# clock.net
KiCad netlist of a schematic drawn in EAGLE
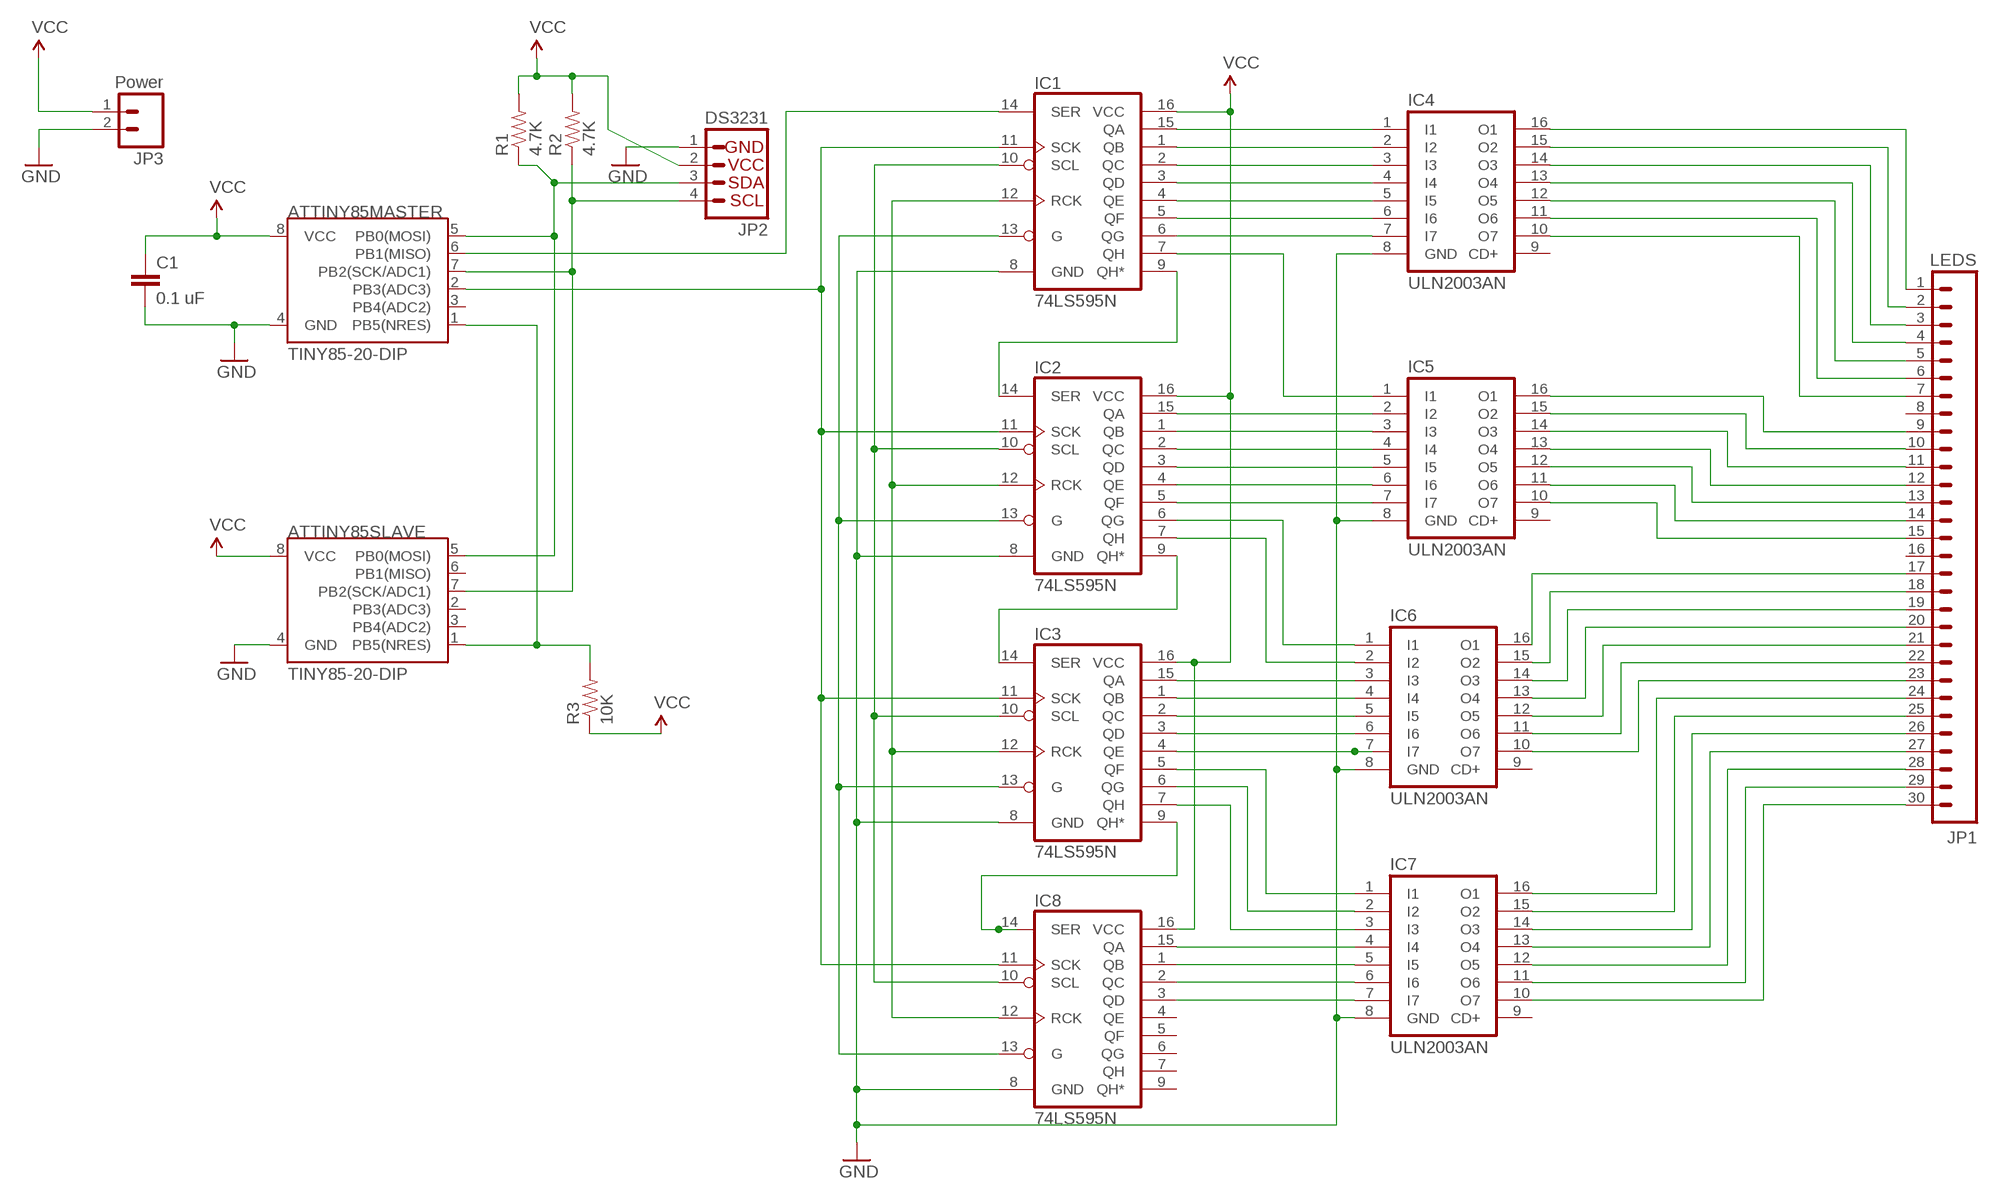
[diagram p0: schematic, sheet 1]

(export (version "E")
  (design (tool "Eeschema 10.0.6"))
  (components
    (comp (ref "ATTINY85MASTER")
      (value "TINY85-20-DIP")
      (footprint "eagle-import:DIP08")
      (libsource (lib "eagle-import") (part "ATTINY45TINY85-20-DIP"))
    )
    (comp (ref "ATTINY85SLAVE")
      (value "TINY85-20-DIP")
      (footprint "eagle-import:DIP08")
      (libsource (lib "eagle-import") (part "ATTINY45TINY85-20-DIP"))
    )
    (comp (ref "C1")
      (value "0.1 uF")
      (footprint "eagle-import:CAP-PTH-SMALL")
      (libsource (lib "eagle-import") (part "CAPPTH"))
    )
    (comp (ref "IC1")
      (value "74LS595N")
      (footprint "eagle-import:DIL16")
      (libsource (lib "eagle-import") (part "74595NLS"))
    )
    (comp (ref "IC2")
      (value "74LS595N")
      (footprint "eagle-import:DIL16")
      (libsource (lib "eagle-import") (part "74595NLS"))
    )
    (comp (ref "IC3")
      (value "74LS595N")
      (footprint "eagle-import:DIL16")
      (libsource (lib "eagle-import") (part "74595NLS"))
    )
    (comp (ref "IC4")
      (value "ULN2003AN")
      (footprint "eagle-import:DIL16")
      (libsource (lib "eagle-import") (part "ULN2003AN"))
    )
    (comp (ref "IC5")
      (value "ULN2003AN")
      (footprint "eagle-import:DIL16")
      (libsource (lib "eagle-import") (part "ULN2003AN"))
    )
    (comp (ref "IC6")
      (value "ULN2003AN")
      (footprint "eagle-import:DIL16")
      (libsource (lib "eagle-import") (part "ULN2003AN"))
    )
    (comp (ref "IC7")
      (value "ULN2003AN")
      (footprint "eagle-import:DIL16")
      (libsource (lib "eagle-import") (part "ULN2003AN"))
    )
    (comp (ref "IC8")
      (value "74LS595N")
      (footprint "eagle-import:DIL16")
      (libsource (lib "eagle-import") (part "74595NLS"))
    )
    (comp (ref "JP1")
      (value "LEDS")
      (footprint "eagle-import:1X30")
      (libsource (lib "eagle-import") (part "M30"))
    )
    (comp (ref "JP2")
      (value "DS3231")
      (footprint "eagle-import:1X04")
      (libsource (lib "eagle-import") (part "I2C_STANDARD"))
    )
    (comp (ref "JP3")
      (value "Power")
      (footprint "eagle-import:1X02_LONGPADS")
      (libsource (lib "eagle-import") (part "M02PTH3"))
    )
    (comp (ref "R1")
      (value "4.7K")
      (footprint "eagle-import:AXIAL-0.4")
      (libsource (lib "eagle-import") (part "RESISTORPTH-1/4W"))
    )
    (comp (ref "R2")
      (value "4.7K")
      (footprint "eagle-import:AXIAL-0.4")
      (libsource (lib "eagle-import") (part "RESISTORPTH-1/4W"))
    )
    (comp (ref "R3")
      (value "10K")
      (footprint "eagle-import:AXIAL-0.4")
      (libsource (lib "eagle-import") (part "RESISTORPTH-1/4W"))
    )
  )
  (nets
    (net (code "1") (name "GND") (class "Default")
      (node (ref "ATTINY85MASTER") (pin "4") (pinfunction "GND_4") (pintype "bidirectional"))
      (node (ref "ATTINY85SLAVE") (pin "4") (pinfunction "GND_4") (pintype "bidirectional"))
      (node (ref "C1") (pin "2") (pinfunction "2_2") (pintype "passive"))
      (node (ref "IC1") (pin "8") (pinfunction "GND_8") (pintype "power_in"))
      (node (ref "IC2") (pin "8") (pinfunction "GND_8") (pintype "power_in"))
      (node (ref "IC3") (pin "8") (pinfunction "GND_8") (pintype "power_in"))
      (node (ref "IC4") (pin "8") (pinfunction "GND_8") (pintype "power_in"))
      (node (ref "IC5") (pin "8") (pinfunction "GND_8") (pintype "power_in"))
      (node (ref "IC6") (pin "8") (pinfunction "GND_8") (pintype "power_in"))
      (node (ref "IC7") (pin "8") (pinfunction "GND_8") (pintype "power_in"))
      (node (ref "IC8") (pin "8") (pinfunction "GND_8") (pintype "power_in"))
      (node (ref "JP2") (pin "1") (pinfunction "1_1") (pintype "passive"))
      (node (ref "JP3") (pin "2") (pinfunction "2_2") (pintype "passive"))
    )
    (net (code "2") (name "Net-(ATTINY85MASTER-PB0(MOSI))") (class "Default")
      (node (ref "ATTINY85MASTER") (pin "5") (pinfunction "PB0(MOSI)_5") (pintype "bidirectional"))
      (node (ref "ATTINY85SLAVE") (pin "5") (pinfunction "PB0(MOSI)_5") (pintype "bidirectional"))
      (node (ref "JP2") (pin "3") (pinfunction "3_3") (pintype "passive"))
      (node (ref "R1") (pin "P$1") (pinfunction "1_P$1") (pintype "passive"))
    )
    (net (code "3") (name "Net-(ATTINY85MASTER-PB1(MISO))") (class "Default")
      (node (ref "ATTINY85MASTER") (pin "6") (pinfunction "PB1(MISO)_6") (pintype "bidirectional"))
      (node (ref "IC1") (pin "14") (pinfunction "SER_14") (pintype "input"))
    )
    (net (code "4") (name "Net-(ATTINY85MASTER-PB2(SCK{slash}ADC1))") (class "Default")
      (node (ref "ATTINY85MASTER") (pin "7") (pinfunction "PB2(SCK/ADC1)_7") (pintype "bidirectional"))
      (node (ref "ATTINY85SLAVE") (pin "7") (pinfunction "PB2(SCK/ADC1)_7") (pintype "bidirectional"))
      (node (ref "JP2") (pin "4") (pinfunction "4_4") (pintype "passive"))
      (node (ref "R2") (pin "P$1") (pinfunction "1_P$1") (pintype "passive"))
    )
    (net (code "5") (name "Net-(ATTINY85MASTER-PB3(ADC3))") (class "Default")
      (node (ref "ATTINY85MASTER") (pin "2") (pinfunction "PB3(ADC3)_2") (pintype "bidirectional"))
      (node (ref "IC1") (pin "11") (pinfunction "SCK_11") (pintype "input"))
      (node (ref "IC2") (pin "11") (pinfunction "SCK_11") (pintype "input"))
      (node (ref "IC3") (pin "11") (pinfunction "SCK_11") (pintype "input"))
      (node (ref "IC8") (pin "11") (pinfunction "SCK_11") (pintype "input"))
    )
    (net (code "6") (name "Net-(ATTINY85MASTER-PB5(NRES))") (class "Default")
      (node (ref "ATTINY85MASTER") (pin "1") (pinfunction "PB5(NRES)_1") (pintype "bidirectional"))
      (node (ref "ATTINY85SLAVE") (pin "1") (pinfunction "PB5(NRES)_1") (pintype "bidirectional"))
      (node (ref "R3") (pin "P$2") (pinfunction "2_P$2") (pintype "passive"))
    )
    (net (code "7") (name "Net-(IC1-G)") (class "Default")
      (node (ref "IC1") (pin "13") (pinfunction "G_13") (pintype "input"))
      (node (ref "IC2") (pin "13") (pinfunction "G_13") (pintype "input"))
      (node (ref "IC3") (pin "13") (pinfunction "G_13") (pintype "input"))
      (node (ref "IC8") (pin "13") (pinfunction "G_13") (pintype "input"))
    )
    (net (code "8") (name "Net-(IC1-QA)") (class "Default")
      (node (ref "IC1") (pin "15") (pinfunction "QA_15") (pintype "tri_state"))
      (node (ref "IC4") (pin "1") (pinfunction "I1_1") (pintype "input"))
    )
    (net (code "9") (name "Net-(IC1-QB)") (class "Default")
      (node (ref "IC1") (pin "1") (pinfunction "QB_1") (pintype "tri_state"))
      (node (ref "IC4") (pin "2") (pinfunction "I2_2") (pintype "input"))
    )
    (net (code "10") (name "Net-(IC1-QC)") (class "Default")
      (node (ref "IC1") (pin "2") (pinfunction "QC_2") (pintype "tri_state"))
      (node (ref "IC4") (pin "3") (pinfunction "I3_3") (pintype "input"))
    )
    (net (code "11") (name "Net-(IC1-QD)") (class "Default")
      (node (ref "IC1") (pin "3") (pinfunction "QD_3") (pintype "tri_state"))
      (node (ref "IC4") (pin "4") (pinfunction "I4_4") (pintype "input"))
    )
    (net (code "12") (name "Net-(IC1-QE)") (class "Default")
      (node (ref "IC1") (pin "4") (pinfunction "QE_4") (pintype "tri_state"))
      (node (ref "IC4") (pin "5") (pinfunction "I5_5") (pintype "input"))
    )
    (net (code "13") (name "Net-(IC1-QF)") (class "Default")
      (node (ref "IC1") (pin "5") (pinfunction "QF_5") (pintype "tri_state"))
      (node (ref "IC4") (pin "6") (pinfunction "I6_6") (pintype "input"))
    )
    (net (code "14") (name "Net-(IC1-QG)") (class "Default")
      (node (ref "IC1") (pin "6") (pinfunction "QG_6") (pintype "tri_state"))
      (node (ref "IC4") (pin "7") (pinfunction "I7_7") (pintype "input"))
    )
    (net (code "15") (name "Net-(IC1-QH)") (class "Default")
      (node (ref "IC1") (pin "7") (pinfunction "QH_7") (pintype "tri_state"))
      (node (ref "IC5") (pin "1") (pinfunction "I1_1") (pintype "input"))
    )
    (net (code "16") (name "Net-(IC1-QH*)") (class "Default")
      (node (ref "IC1") (pin "9") (pinfunction "QH*_9") (pintype "tri_state"))
      (node (ref "IC2") (pin "14") (pinfunction "SER_14") (pintype "input"))
    )
    (net (code "17") (name "Net-(IC1-RCK)") (class "Default")
      (node (ref "IC1") (pin "12") (pinfunction "RCK_12") (pintype "input"))
      (node (ref "IC2") (pin "12") (pinfunction "RCK_12") (pintype "input"))
      (node (ref "IC3") (pin "12") (pinfunction "RCK_12") (pintype "input"))
      (node (ref "IC8") (pin "12") (pinfunction "RCK_12") (pintype "input"))
    )
    (net (code "18") (name "Net-(IC1-SCL)") (class "Default")
      (node (ref "IC1") (pin "10") (pinfunction "SCL_10") (pintype "input"))
      (node (ref "IC2") (pin "10") (pinfunction "SCL_10") (pintype "input"))
      (node (ref "IC3") (pin "10") (pinfunction "SCL_10") (pintype "input"))
      (node (ref "IC8") (pin "10") (pinfunction "SCL_10") (pintype "input"))
    )
    (net (code "19") (name "Net-(IC2-QA)") (class "Default")
      (node (ref "IC2") (pin "15") (pinfunction "QA_15") (pintype "tri_state"))
      (node (ref "IC5") (pin "2") (pinfunction "I2_2") (pintype "input"))
    )
    (net (code "20") (name "Net-(IC2-QB)") (class "Default")
      (node (ref "IC2") (pin "1") (pinfunction "QB_1") (pintype "tri_state"))
      (node (ref "IC5") (pin "3") (pinfunction "I3_3") (pintype "input"))
    )
    (net (code "21") (name "Net-(IC2-QC)") (class "Default")
      (node (ref "IC2") (pin "2") (pinfunction "QC_2") (pintype "tri_state"))
      (node (ref "IC5") (pin "4") (pinfunction "I4_4") (pintype "input"))
    )
    (net (code "22") (name "Net-(IC2-QD)") (class "Default")
      (node (ref "IC2") (pin "3") (pinfunction "QD_3") (pintype "tri_state"))
      (node (ref "IC5") (pin "5") (pinfunction "I5_5") (pintype "input"))
    )
    (net (code "23") (name "Net-(IC2-QE)") (class "Default")
      (node (ref "IC2") (pin "4") (pinfunction "QE_4") (pintype "tri_state"))
      (node (ref "IC5") (pin "6") (pinfunction "I6_6") (pintype "input"))
    )
    (net (code "24") (name "Net-(IC2-QF)") (class "Default")
      (node (ref "IC2") (pin "5") (pinfunction "QF_5") (pintype "tri_state"))
      (node (ref "IC5") (pin "7") (pinfunction "I7_7") (pintype "input"))
    )
    (net (code "25") (name "Net-(IC2-QG)") (class "Default")
      (node (ref "IC2") (pin "6") (pinfunction "QG_6") (pintype "tri_state"))
      (node (ref "IC6") (pin "1") (pinfunction "I1_1") (pintype "input"))
    )
    (net (code "26") (name "Net-(IC2-QH)") (class "Default")
      (node (ref "IC2") (pin "7") (pinfunction "QH_7") (pintype "tri_state"))
      (node (ref "IC6") (pin "2") (pinfunction "I2_2") (pintype "input"))
    )
    (net (code "27") (name "Net-(IC2-QH*)") (class "Default")
      (node (ref "IC2") (pin "9") (pinfunction "QH*_9") (pintype "tri_state"))
      (node (ref "IC3") (pin "14") (pinfunction "SER_14") (pintype "input"))
    )
    (net (code "28") (name "Net-(IC3-QA)") (class "Default")
      (node (ref "IC3") (pin "15") (pinfunction "QA_15") (pintype "tri_state"))
      (node (ref "IC6") (pin "3") (pinfunction "I3_3") (pintype "input"))
    )
    (net (code "29") (name "Net-(IC3-QB)") (class "Default")
      (node (ref "IC3") (pin "1") (pinfunction "QB_1") (pintype "tri_state"))
      (node (ref "IC6") (pin "4") (pinfunction "I4_4") (pintype "input"))
    )
    (net (code "30") (name "Net-(IC3-QC)") (class "Default")
      (node (ref "IC3") (pin "2") (pinfunction "QC_2") (pintype "tri_state"))
      (node (ref "IC6") (pin "5") (pinfunction "I5_5") (pintype "input"))
    )
    (net (code "31") (name "Net-(IC3-QD)") (class "Default")
      (node (ref "IC3") (pin "3") (pinfunction "QD_3") (pintype "tri_state"))
      (node (ref "IC6") (pin "6") (pinfunction "I6_6") (pintype "input"))
    )
    (net (code "32") (name "Net-(IC3-QE)") (class "Default")
      (node (ref "IC3") (pin "4") (pinfunction "QE_4") (pintype "tri_state"))
      (node (ref "IC6") (pin "7") (pinfunction "I7_7") (pintype "input"))
    )
    (net (code "33") (name "Net-(IC3-QF)") (class "Default")
      (node (ref "IC3") (pin "5") (pinfunction "QF_5") (pintype "tri_state"))
      (node (ref "IC7") (pin "1") (pinfunction "I1_1") (pintype "input"))
    )
    (net (code "34") (name "Net-(IC3-QG)") (class "Default")
      (node (ref "IC3") (pin "6") (pinfunction "QG_6") (pintype "tri_state"))
      (node (ref "IC7") (pin "2") (pinfunction "I2_2") (pintype "input"))
    )
    (net (code "35") (name "Net-(IC3-QH)") (class "Default")
      (node (ref "IC3") (pin "7") (pinfunction "QH_7") (pintype "tri_state"))
      (node (ref "IC7") (pin "3") (pinfunction "I3_3") (pintype "input"))
    )
    (net (code "36") (name "Net-(IC3-QH*)") (class "Default")
      (node (ref "IC3") (pin "9") (pinfunction "QH*_9") (pintype "tri_state"))
      (node (ref "IC8") (pin "14") (pinfunction "SER_14") (pintype "input"))
    )
    (net (code "37") (name "Net-(IC4-O1)") (class "Default")
      (node (ref "IC4") (pin "16") (pinfunction "O1_16") (pintype "open_collector"))
      (node (ref "JP1") (pin "1") (pinfunction "1_1") (pintype "passive"))
    )
    (net (code "38") (name "Net-(IC4-O2)") (class "Default")
      (node (ref "IC4") (pin "15") (pinfunction "O2_15") (pintype "open_collector"))
      (node (ref "JP1") (pin "2") (pinfunction "2_2") (pintype "passive"))
    )
    (net (code "39") (name "Net-(IC4-O3)") (class "Default")
      (node (ref "IC4") (pin "14") (pinfunction "O3_14") (pintype "open_collector"))
      (node (ref "JP1") (pin "3") (pinfunction "3_3") (pintype "passive"))
    )
    (net (code "40") (name "Net-(IC4-O4)") (class "Default")
      (node (ref "IC4") (pin "13") (pinfunction "O4_13") (pintype "open_collector"))
      (node (ref "JP1") (pin "4") (pinfunction "4_4") (pintype "passive"))
    )
    (net (code "41") (name "Net-(IC4-O5)") (class "Default")
      (node (ref "IC4") (pin "12") (pinfunction "O5_12") (pintype "open_collector"))
      (node (ref "JP1") (pin "5") (pinfunction "5_5") (pintype "passive"))
    )
    (net (code "42") (name "Net-(IC4-O6)") (class "Default")
      (node (ref "IC4") (pin "11") (pinfunction "O6_11") (pintype "open_collector"))
      (node (ref "JP1") (pin "6") (pinfunction "6_6") (pintype "passive"))
    )
    (net (code "43") (name "Net-(IC4-O7)") (class "Default")
      (node (ref "IC4") (pin "10") (pinfunction "O7_10") (pintype "open_collector"))
      (node (ref "JP1") (pin "7") (pinfunction "7_7") (pintype "passive"))
    )
    (net (code "44") (name "Net-(IC5-O1)") (class "Default")
      (node (ref "IC5") (pin "16") (pinfunction "O1_16") (pintype "open_collector"))
      (node (ref "JP1") (pin "9") (pinfunction "9_9") (pintype "passive"))
    )
    (net (code "45") (name "Net-(IC5-O2)") (class "Default")
      (node (ref "IC5") (pin "15") (pinfunction "O2_15") (pintype "open_collector"))
      (node (ref "JP1") (pin "10") (pinfunction "10_10") (pintype "passive"))
    )
    (net (code "46") (name "Net-(IC5-O3)") (class "Default")
      (node (ref "IC5") (pin "14") (pinfunction "O3_14") (pintype "open_collector"))
      (node (ref "JP1") (pin "11") (pinfunction "11_11") (pintype "passive"))
    )
    (net (code "47") (name "Net-(IC5-O4)") (class "Default")
      (node (ref "IC5") (pin "13") (pinfunction "O4_13") (pintype "open_collector"))
      (node (ref "JP1") (pin "12") (pinfunction "12_12") (pintype "passive"))
    )
    (net (code "48") (name "Net-(IC5-O5)") (class "Default")
      (node (ref "IC5") (pin "12") (pinfunction "O5_12") (pintype "open_collector"))
      (node (ref "JP1") (pin "13") (pinfunction "13_13") (pintype "passive"))
    )
    (net (code "49") (name "Net-(IC5-O6)") (class "Default")
      (node (ref "IC5") (pin "11") (pinfunction "O6_11") (pintype "open_collector"))
      (node (ref "JP1") (pin "14") (pinfunction "14_14") (pintype "passive"))
    )
    (net (code "50") (name "Net-(IC5-O7)") (class "Default")
      (node (ref "IC5") (pin "10") (pinfunction "O7_10") (pintype "open_collector"))
      (node (ref "JP1") (pin "15") (pinfunction "15_15") (pintype "passive"))
    )
    (net (code "51") (name "Net-(IC6-O1)") (class "Default")
      (node (ref "IC6") (pin "16") (pinfunction "O1_16") (pintype "open_collector"))
      (node (ref "JP1") (pin "17") (pinfunction "17_17") (pintype "passive"))
    )
    (net (code "52") (name "Net-(IC6-O2)") (class "Default")
      (node (ref "IC6") (pin "15") (pinfunction "O2_15") (pintype "open_collector"))
      (node (ref "JP1") (pin "18") (pinfunction "18_18") (pintype "passive"))
    )
    (net (code "53") (name "Net-(IC6-O3)") (class "Default")
      (node (ref "IC6") (pin "14") (pinfunction "O3_14") (pintype "open_collector"))
      (node (ref "JP1") (pin "19") (pinfunction "19_19") (pintype "passive"))
    )
    (net (code "54") (name "Net-(IC6-O4)") (class "Default")
      (node (ref "IC6") (pin "13") (pinfunction "O4_13") (pintype "open_collector"))
      (node (ref "JP1") (pin "20") (pinfunction "20_20") (pintype "passive"))
    )
    (net (code "55") (name "Net-(IC6-O5)") (class "Default")
      (node (ref "IC6") (pin "12") (pinfunction "O5_12") (pintype "open_collector"))
      (node (ref "JP1") (pin "21") (pinfunction "21_21") (pintype "passive"))
    )
    (net (code "56") (name "Net-(IC6-O6)") (class "Default")
      (node (ref "IC6") (pin "11") (pinfunction "O6_11") (pintype "open_collector"))
      (node (ref "JP1") (pin "22") (pinfunction "22_22") (pintype "passive"))
    )
    (net (code "57") (name "Net-(IC6-O7)") (class "Default")
      (node (ref "IC6") (pin "10") (pinfunction "O7_10") (pintype "open_collector"))
      (node (ref "JP1") (pin "23") (pinfunction "23_23") (pintype "passive"))
    )
    (net (code "58") (name "Net-(IC7-I4)") (class "Default")
      (node (ref "IC7") (pin "4") (pinfunction "I4_4") (pintype "input"))
      (node (ref "IC8") (pin "15") (pinfunction "QA_15") (pintype "tri_state"))
    )
    (net (code "59") (name "Net-(IC7-I5)") (class "Default")
      (node (ref "IC7") (pin "5") (pinfunction "I5_5") (pintype "input"))
      (node (ref "IC8") (pin "1") (pinfunction "QB_1") (pintype "tri_state"))
    )
    (net (code "60") (name "Net-(IC7-I6)") (class "Default")
      (node (ref "IC7") (pin "6") (pinfunction "I6_6") (pintype "input"))
      (node (ref "IC8") (pin "2") (pinfunction "QC_2") (pintype "tri_state"))
    )
    (net (code "61") (name "Net-(IC7-I7)") (class "Default")
      (node (ref "IC7") (pin "7") (pinfunction "I7_7") (pintype "input"))
      (node (ref "IC8") (pin "3") (pinfunction "QD_3") (pintype "tri_state"))
    )
    (net (code "62") (name "Net-(IC7-O1)") (class "Default")
      (node (ref "IC7") (pin "16") (pinfunction "O1_16") (pintype "open_collector"))
      (node (ref "JP1") (pin "24") (pinfunction "24_24") (pintype "passive"))
    )
    (net (code "63") (name "Net-(IC7-O2)") (class "Default")
      (node (ref "IC7") (pin "15") (pinfunction "O2_15") (pintype "open_collector"))
      (node (ref "JP1") (pin "25") (pinfunction "25_25") (pintype "passive"))
    )
    (net (code "64") (name "Net-(IC7-O3)") (class "Default")
      (node (ref "IC7") (pin "14") (pinfunction "O3_14") (pintype "open_collector"))
      (node (ref "JP1") (pin "26") (pinfunction "26_26") (pintype "passive"))
    )
    (net (code "65") (name "Net-(IC7-O4)") (class "Default")
      (node (ref "IC7") (pin "13") (pinfunction "O4_13") (pintype "open_collector"))
      (node (ref "JP1") (pin "27") (pinfunction "27_27") (pintype "passive"))
    )
    (net (code "66") (name "Net-(IC7-O5)") (class "Default")
      (node (ref "IC7") (pin "12") (pinfunction "O5_12") (pintype "open_collector"))
      (node (ref "JP1") (pin "28") (pinfunction "28_28") (pintype "passive"))
    )
    (net (code "67") (name "Net-(IC7-O6)") (class "Default")
      (node (ref "IC7") (pin "11") (pinfunction "O6_11") (pintype "open_collector"))
      (node (ref "JP1") (pin "29") (pinfunction "29_29") (pintype "passive"))
    )
    (net (code "68") (name "Net-(IC7-O7)") (class "Default")
      (node (ref "IC7") (pin "10") (pinfunction "O7_10") (pintype "open_collector"))
      (node (ref "JP1") (pin "30") (pinfunction "30_30") (pintype "passive"))
    )
    (net (code "69") (name "VCC") (class "Default")
      (node (ref "ATTINY85MASTER") (pin "8") (pinfunction "VCC_8") (pintype "bidirectional"))
      (node (ref "ATTINY85SLAVE") (pin "8") (pinfunction "VCC_8") (pintype "bidirectional"))
      (node (ref "C1") (pin "1") (pinfunction "1_1") (pintype "passive"))
      (node (ref "IC1") (pin "16") (pinfunction "VCC_16") (pintype "power_in"))
      (node (ref "IC2") (pin "16") (pinfunction "VCC_16") (pintype "power_in"))
      (node (ref "IC3") (pin "16") (pinfunction "VCC_16") (pintype "power_in"))
      (node (ref "IC8") (pin "16") (pinfunction "VCC_16") (pintype "power_in"))
      (node (ref "JP2") (pin "2") (pinfunction "2_2") (pintype "passive"))
      (node (ref "JP3") (pin "1") (pinfunction "1_1") (pintype "passive"))
      (node (ref "R1") (pin "P$2") (pinfunction "2_P$2") (pintype "passive"))
      (node (ref "R2") (pin "P$2") (pinfunction "2_P$2") (pintype "passive"))
      (node (ref "R3") (pin "P$1") (pinfunction "1_P$1") (pintype "passive"))
    )
    (net (code "70") (name "unconnected-(ATTINY85MASTER-PB4(ADC2)-Pad3)") (class "Default")
      (node (ref "ATTINY85MASTER") (pin "3") (pinfunction "PB4(ADC2)_3") (pintype "bidirectional"))
    )
    (net (code "71") (name "unconnected-(ATTINY85SLAVE-PB1(MISO)-Pad6)") (class "Default")
      (node (ref "ATTINY85SLAVE") (pin "6") (pinfunction "PB1(MISO)_6") (pintype "bidirectional"))
    )
    (net (code "72") (name "unconnected-(ATTINY85SLAVE-PB3(ADC3)-Pad2)") (class "Default")
      (node (ref "ATTINY85SLAVE") (pin "2") (pinfunction "PB3(ADC3)_2") (pintype "bidirectional"))
    )
    (net (code "73") (name "unconnected-(ATTINY85SLAVE-PB4(ADC2)-Pad3)") (class "Default")
      (node (ref "ATTINY85SLAVE") (pin "3") (pinfunction "PB4(ADC2)_3") (pintype "bidirectional"))
    )
    (net (code "74") (name "unconnected-(IC4-CD+-Pad9)") (class "Default")
      (node (ref "IC4") (pin "9") (pinfunction "CD+_9") (pintype "passive"))
    )
    (net (code "75") (name "unconnected-(IC5-CD+-Pad9)") (class "Default")
      (node (ref "IC5") (pin "9") (pinfunction "CD+_9") (pintype "passive"))
    )
    (net (code "76") (name "unconnected-(IC6-CD+-Pad9)") (class "Default")
      (node (ref "IC6") (pin "9") (pinfunction "CD+_9") (pintype "passive"))
    )
    (net (code "77") (name "unconnected-(IC7-CD+-Pad9)") (class "Default")
      (node (ref "IC7") (pin "9") (pinfunction "CD+_9") (pintype "passive"))
    )
    (net (code "78") (name "unconnected-(IC8-QE-Pad4)") (class "Default")
      (node (ref "IC8") (pin "4") (pinfunction "QE_4") (pintype "tri_state"))
    )
    (net (code "79") (name "unconnected-(IC8-QF-Pad5)") (class "Default")
      (node (ref "IC8") (pin "5") (pinfunction "QF_5") (pintype "tri_state"))
    )
    (net (code "80") (name "unconnected-(IC8-QG-Pad6)") (class "Default")
      (node (ref "IC8") (pin "6") (pinfunction "QG_6") (pintype "tri_state"))
    )
    (net (code "81") (name "unconnected-(IC8-QH*-Pad9)") (class "Default")
      (node (ref "IC8") (pin "9") (pinfunction "QH*_9") (pintype "tri_state"))
    )
    (net (code "82") (name "unconnected-(IC8-QH-Pad7)") (class "Default")
      (node (ref "IC8") (pin "7") (pinfunction "QH_7") (pintype "tri_state"))
    )
    (net (code "83") (name "unconnected-(JP1-Pad8)") (class "Default")
      (node (ref "JP1") (pin "8") (pinfunction "8_8") (pintype "passive"))
    )
    (net (code "84") (name "unconnected-(JP1-Pad16)") (class "Default")
      (node (ref "JP1") (pin "16") (pinfunction "16_16") (pintype "passive"))
    )
  )
)
